# Power.net
KiCad netlist of a schematic drawn in Altium Designer
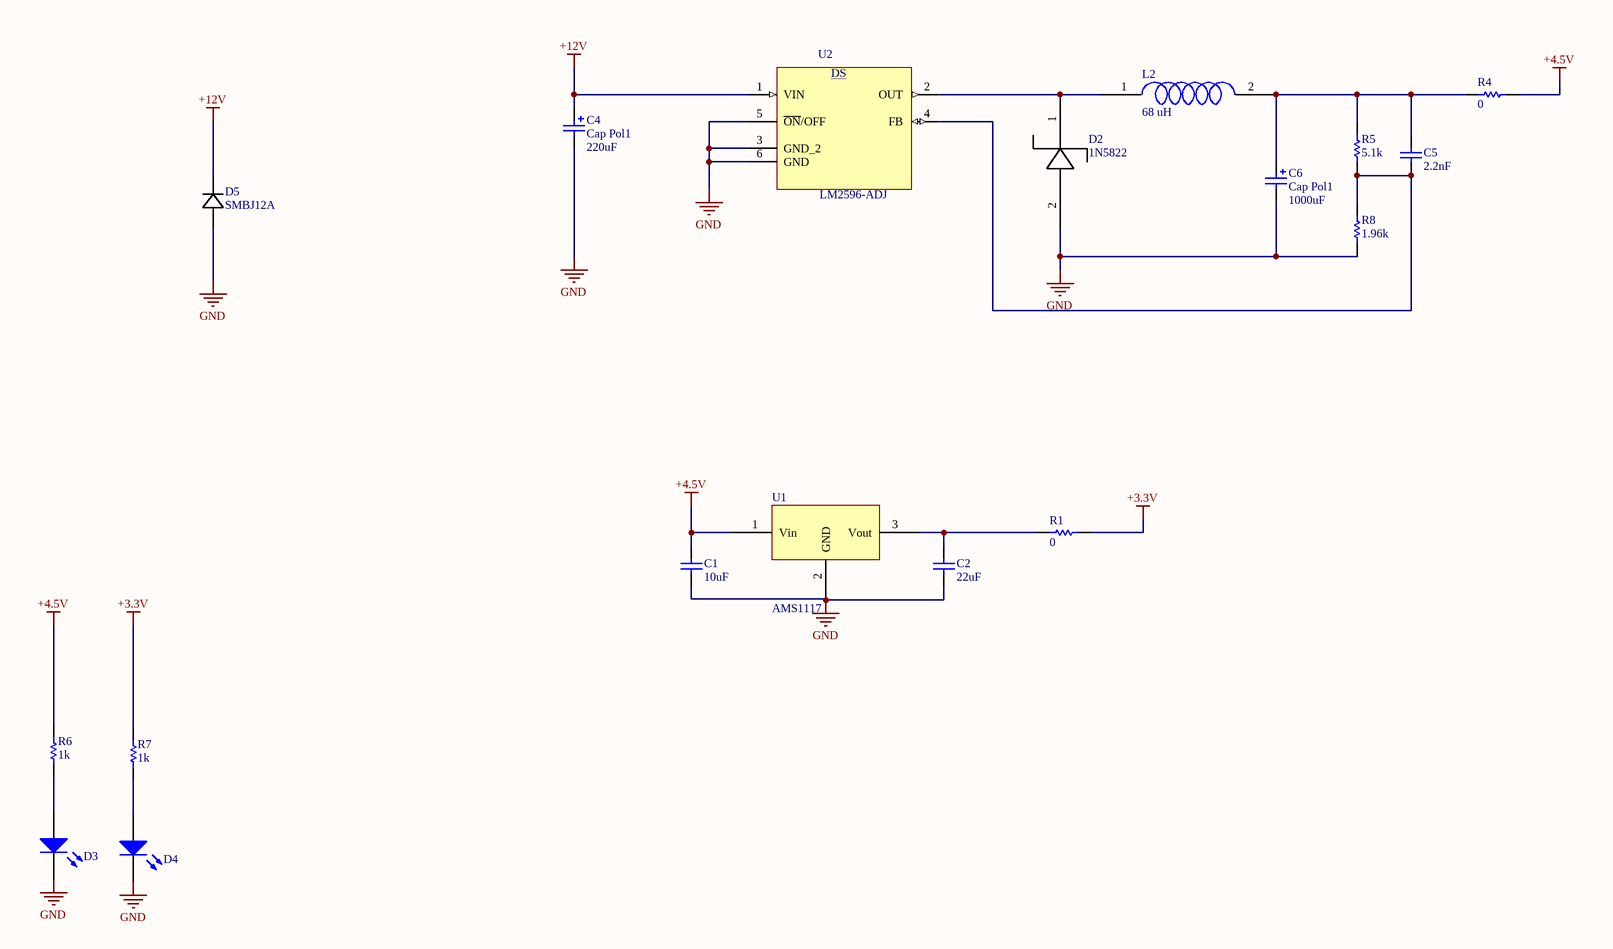
[diagram p0: Power.SchDoc]

(export (version "E")
  (design (tool "Eeschema 10.0.6"))
  (components
    (comp (ref "C1")
      (value "10uF")
      (footprint "C-1206")
      (description "Capacitor")
      (fields (field (name "Comment") "C-1206") (field (name "PUBLISHER") "Altium Limited"))
      (libsource (lib "AfraLIB") (part "C-1206"))
    )
    (comp (ref "C2")
      (value "22uF")
      (footprint "C-1206")
      (description "Capacitor")
      (fields (field (name "Comment") "C-1206") (field (name "PUBLISHER") "Altium Limited"))
      (libsource (lib "AfraLIB") (part "C-1206"))
    )
    (comp (ref "C4")
      (value "Cap Pol1")
      (footprint "RB5-10.5")
      (description "Polarized Capacitor (Radial)")
      (fields (field (name "ALTIUM_VALUE") "220uF") (field (name "PUBLISHER") "Altium Limited"))
      (libsource (lib "AfraLIB") (part "Cap Pol1"))
    )
    (comp (ref "C5")
      (value "2.2nF")
      (footprint "C-805")
      (description "Capacitor")
      (fields (field (name "Comment") "C-805") (field (name "PUBLISHER") "Altium Limited"))
      (libsource (lib "AfraLIB") (part "C-805"))
    )
    (comp (ref "C6")
      (value "Cap Pol1")
      (footprint "RB5-10.5")
      (description "Polarized Capacitor (Radial)")
      (fields (field (name "ALTIUM_VALUE") "1000uF") (field (name "PUBLISHER") "Altium Limited"))
      (libsource (lib "AfraLIB") (part "Cap Pol1"))
    )
    (comp (ref "D2") (value "1N5822") (footprint "1N5822") (libsource (lib "AfraLIB") (part "1N5822")))
    (comp (ref "D3")
      (value "LED-805")
      (footprint "LED-805")
      (description "LED Size 805")
      (fields (field (name "PUBLISHER") "Altium Limited"))
      (libsource (lib "AfraLIB") (part "LED-805"))
    )
    (comp (ref "D4")
      (value "LED-805")
      (footprint "LED-805")
      (description "LED Size 805")
      (fields (field (name "PUBLISHER") "Altium Limited"))
      (libsource (lib "AfraLIB") (part "LED-805"))
    )
    (comp (ref "D5")
      (value "SMBJ12A")
      (footprint "SMB")
      (description "No Description Available")
      (fields
        (field (name "MANUFACTURER_PART_NUMBER") "SMBJ12A-13-F")
        (field (name "COPYRIGHT") "Copyright (C) 2018 Accelerated Designs. All rights reserved")
      )
      (libsource (lib "AfraLIB") (part "SMBJ12A"))
    )
    (comp (ref "L2")
      (value "68 uH")
      (footprint "Inductor")
      (description "Power inductor")
      (libsource (lib "MFHLIB") (part "Inductor"))
    )
    (comp (ref "R1")
      (value "0")
      (footprint "R-1206")
      (description "Resistor")
      (fields (field (name "Comment") "R-1206"))
      (libsource (lib "AfraLIB") (part "R-1206"))
    )
    (comp (ref "R4")
      (value "0")
      (footprint "R-1206")
      (description "Resistor")
      (fields (field (name "Comment") "R-1206"))
      (libsource (lib "AfraLIB") (part "R-1206"))
    )
    (comp (ref "R5")
      (value "5.1k")
      (footprint "R-805")
      (description "Resistor")
      (fields (field (name "Comment") "R-805"))
      (libsource (lib "AfraLIB") (part "R-805"))
    )
    (comp (ref "R6")
      (value "1k")
      (footprint "R-805")
      (description "Resistor")
      (fields (field (name "Comment") "R-805"))
      (libsource (lib "AfraLIB") (part "R-805"))
    )
    (comp (ref "R7")
      (value "1k")
      (footprint "R-805")
      (description "Resistor")
      (fields (field (name "Comment") "R-805"))
      (libsource (lib "AfraLIB") (part "R-805"))
    )
    (comp (ref "R8")
      (value "1.96k")
      (footprint "R-805")
      (description "Resistor")
      (fields (field (name "Comment") "R-805"))
      (libsource (lib "AfraLIB") (part "R-805"))
    )
    (comp (ref "U1")
      (value "AMS1117")
      (footprint "AMS1117")
      (description "3.3v regulator")
      (libsource (lib "AfraLIB") (part "AMS1117"))
    )
    (comp (ref "U2")
      (value "LM2596-ADJ")
      (footprint "LM2596SX")
      (description "SIMPLE SWITCHER Power Converter 150 KHz 3A Step-Down Voltage Regulator 5-DDPAK/TO-263")
      (fields (field (name "MF") "Texas Instruments"))
      (libsource (lib "AfraLIB") (part "LM2596-ADJ"))
    )
  )
  (nets
    (net (code "1") (name "+3.3V") (class "Default")
      (node (ref "R1") (pin "2") (pinfunction "2_2") (pintype "passive"))
      (node (ref "R7") (pin "2") (pinfunction "2_2") (pintype "passive"))
    )
    (net (code "2") (name "+4.5V") (class "Default")
      (node (ref "C1") (pin "2") (pinfunction "2_2") (pintype "passive"))
      (node (ref "R4") (pin "2") (pinfunction "2_2") (pintype "passive"))
      (node (ref "R6") (pin "2") (pinfunction "2_2") (pintype "passive"))
      (node (ref "U1") (pin "1") (pinfunction "Vin_1") (pintype "passive"))
    )
    (net (code "3") (name "+12V") (class "Default")
      (node (ref "C4") (pin "1") (pinfunction "1_1") (pintype "passive"))
      (node (ref "D5") (pin "1") (pinfunction "1_1") (pintype "passive"))
      (node (ref "U2") (pin "1") (pinfunction "VIN_1") (pintype "input"))
    )
    (net (code "4") (name "GND") (class "Default")
      (node (ref "C1") (pin "1") (pinfunction "1_1") (pintype "passive"))
      (node (ref "C2") (pin "1") (pinfunction "1_1") (pintype "passive"))
      (node (ref "C4") (pin "2") (pinfunction "2_2") (pintype "passive"))
      (node (ref "C6") (pin "2") (pinfunction "2_2") (pintype "passive"))
      (node (ref "D2") (pin "2") (pintype "passive"))
      (node (ref "D3") (pin "2") (pinfunction "K_2") (pintype "passive"))
      (node (ref "D4") (pin "2") (pinfunction "K_2") (pintype "passive"))
      (node (ref "D5") (pin "2") (pinfunction "2_2") (pintype "passive"))
      (node (ref "R8") (pin "2") (pinfunction "2_2") (pintype "passive"))
      (node (ref "U1") (pin "2") (pinfunction "GND_2") (pintype "passive"))
      (node (ref "U2") (pin "3") (pinfunction "GND_2_3") (pintype "passive"))
      (node (ref "U2") (pin "5") (pinfunction "~{ON}/OFF_5") (pintype "passive"))
      (node (ref "U2") (pin "6") (pinfunction "GND_6") (pintype "passive"))
    )
    (net (code "5") (name "Net-(C5-Pad2)") (class "Default")
      (node (ref "C5") (pin "2") (pinfunction "2_2") (pintype "passive"))
      (node (ref "C6") (pin "1") (pinfunction "1_1") (pintype "passive"))
      (node (ref "L2") (pin "2") (pintype "passive"))
      (node (ref "R4") (pin "1") (pinfunction "1_1") (pintype "passive"))
      (node (ref "R5") (pin "1") (pinfunction "1_1") (pintype "passive"))
    )
    (net (code "6") (name "Net-(D3-A)") (class "Default")
      (node (ref "D3") (pin "1") (pinfunction "A_1") (pintype "passive"))
      (node (ref "R6") (pin "1") (pinfunction "1_1") (pintype "passive"))
    )
    (net (code "7") (name "Net-(D4-A)") (class "Default")
      (node (ref "D4") (pin "1") (pinfunction "A_1") (pintype "passive"))
      (node (ref "R7") (pin "1") (pinfunction "1_1") (pintype "passive"))
    )
    (net (code "8") (name "Net-(U1-Vout)") (class "Default")
      (node (ref "C2") (pin "2") (pinfunction "2_2") (pintype "passive"))
      (node (ref "R1") (pin "1") (pinfunction "1_1") (pintype "passive"))
      (node (ref "U1") (pin "3") (pinfunction "Vout_3") (pintype "passive"))
    )
    (net (code "9") (name "Net-(U2-FB)") (class "Default")
      (node (ref "C5") (pin "1") (pinfunction "1_1") (pintype "passive"))
      (node (ref "R5") (pin "2") (pinfunction "2_2") (pintype "passive"))
      (node (ref "R8") (pin "1") (pinfunction "1_1") (pintype "passive"))
      (node (ref "U2") (pin "4") (pinfunction "FB_4") (pintype "bidirectional"))
    )
    (net (code "10") (name "Net-(U2-OUT)") (class "Default")
      (node (ref "D2") (pin "1") (pintype "passive"))
      (node (ref "L2") (pin "1") (pintype "passive"))
      (node (ref "U2") (pin "2") (pinfunction "OUT_2") (pintype "output"))
    )
  )
)
